# BSPD.net
KiCad netlist of a schematic drawn in Altium Designer
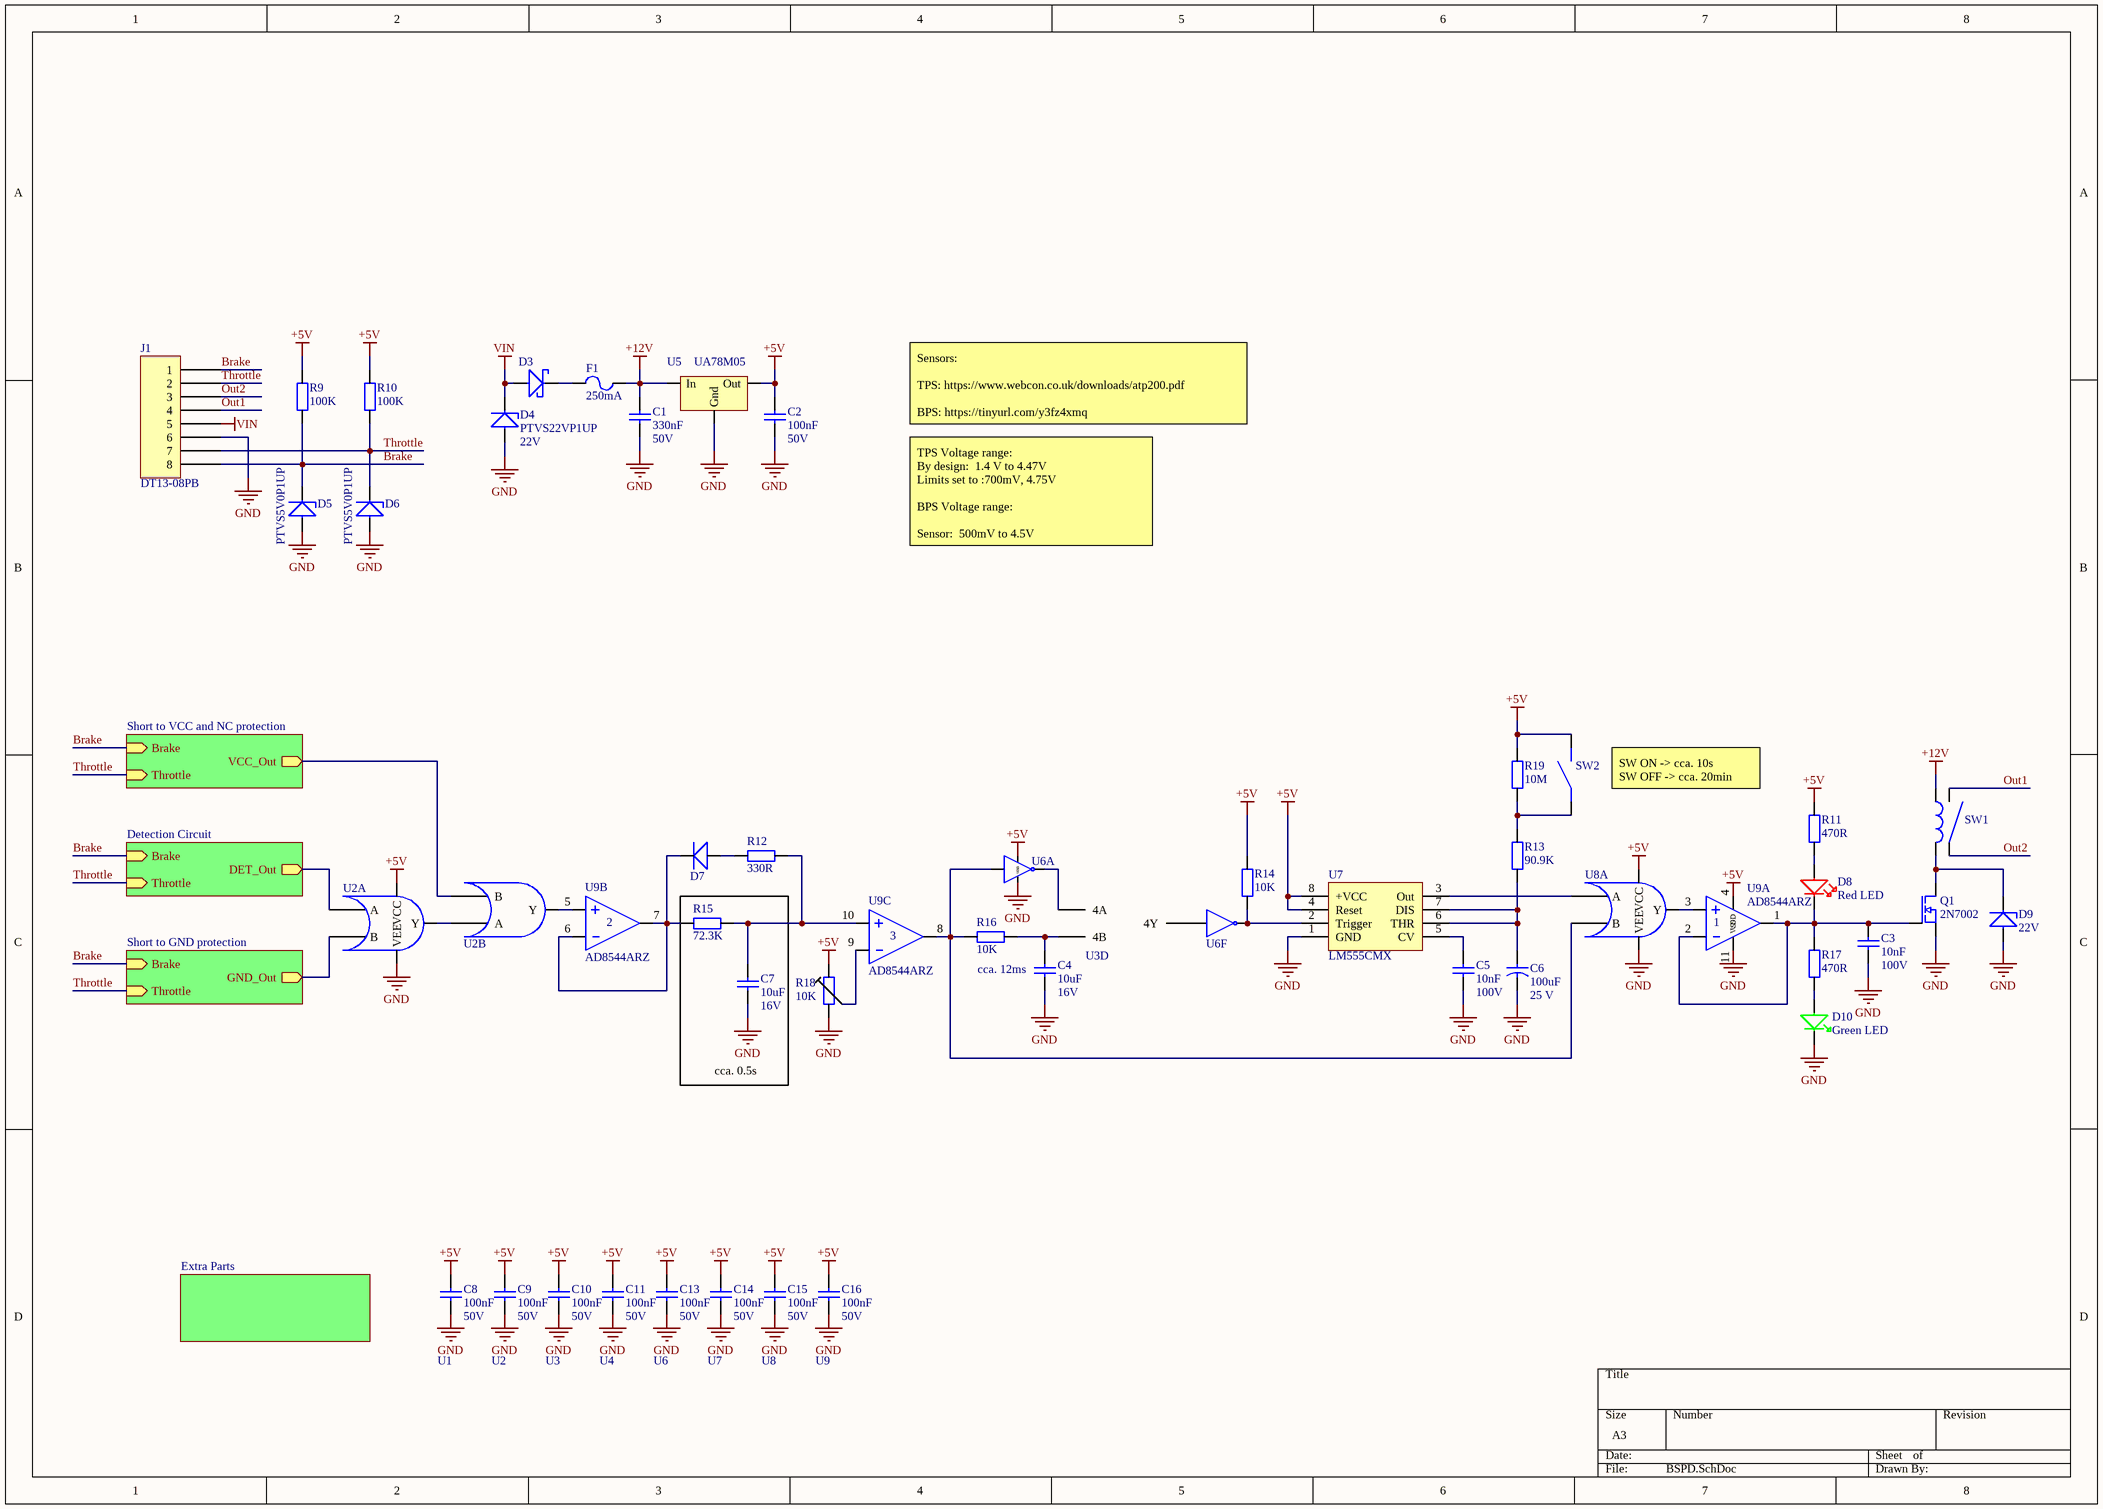
[diagram p0: BSPD.SchDoc]

(export (version "E")
  (design (tool "Eeschema 10.0.6"))
  (components
    (comp (ref "C1")
      (value "330nF")
      (footprint "CAPC320X160X90L50N")
      (fields
        (field (name "PART NUMBER") "C_1206_330nF_50V")
        (field (name "VOLTAGE RATING") "50V")
        (field (name "MANUFACTURER PART NUMBER") "1206B334K500CT")
      )
      (libsource (lib "FR") (part "Capacitor_NP"))
    )
    (comp (ref "C2")
      (value "100nF")
      (footprint "CAPC160X80X87L35N")
      (fields
        (field (name "PART NUMBER") "C_0603_100nF_50V")
        (field (name "VOLTAGE RATING") "50V")
        (field (name "MANUFACTURER PART NUMBER") "CC0603MRY5V9BB104")
      )
      (libsource (lib "FR") (part "Capacitor_NP"))
    )
    (comp (ref "C3")
      (value "10nF")
      (footprint "CAPC160X80X87L35N")
      (fields
        (field (name "PART NUMBER") "C_0603_10nF_100V")
        (field (name "VOLTAGE RATING") "100V")
        (field (name "MANUFACTURER PART NUMBER") "885012206114")
      )
      (libsource (lib "FR") (part "Capacitor_NP"))
    )
    (comp (ref "C4")
      (value "10uF")
      (footprint "CAPC160X80X90L40N")
      (fields
        (field (name "PART NUMBER") "C_0603_10uF_16V")
        (field (name "VOLTAGE RATING") "16V")
        (field (name "MANUFACTURER PART NUMBER") "GRM188R61C106KAALD")
      )
      (libsource (lib "FR") (part "Capacitor_NP"))
    )
    (comp (ref "C5")
      (value "10nF")
      (footprint "CAPC160X80X87L35N")
      (fields
        (field (name "PART NUMBER") "C_0603_10nF_100V")
        (field (name "VOLTAGE RATING") "100V")
        (field (name "MANUFACTURER PART NUMBER") "885012206114")
      )
      (libsource (lib "FR") (part "Capacitor_NP"))
    )
    (comp (ref "C6")
      (value "100uF")
      (footprint "CAPAE660X770D660L220X65N")
      (fields
        (field (name "PART NUMBER") "C_100uF_25V")
        (field (name "VOLTAGE RATING") "25 V")
        (field (name "MANUFACTURER PART NUMBER") "865080445010")
      )
      (libsource (lib "FR") (part "Capacitor_P"))
    )
    (comp (ref "C7")
      (value "10uF")
      (footprint "CAPC160X80X90L40N")
      (fields
        (field (name "PART NUMBER") "C_0603_10uF_16V")
        (field (name "VOLTAGE RATING") "16V")
        (field (name "MANUFACTURER PART NUMBER") "GRM188R61C106KAALD")
      )
      (libsource (lib "FR") (part "Capacitor_NP"))
    )
    (comp (ref "C8")
      (value "100nF")
      (footprint "CAPC160X80X87L35N")
      (fields
        (field (name "PART NUMBER") "C_0603_100nF_50V")
        (field (name "VOLTAGE RATING") "50V")
        (field (name "MANUFACTURER PART NUMBER") "CC0603MRY5V9BB104")
      )
      (libsource (lib "FR") (part "Capacitor_NP"))
    )
    (comp (ref "C9")
      (value "100nF")
      (footprint "CAPC160X80X87L35N")
      (fields
        (field (name "PART NUMBER") "C_0603_100nF_50V")
        (field (name "VOLTAGE RATING") "50V")
        (field (name "MANUFACTURER PART NUMBER") "CC0603MRY5V9BB104")
      )
      (libsource (lib "FR") (part "Capacitor_NP"))
    )
    (comp (ref "C10")
      (value "100nF")
      (footprint "CAPC160X80X87L35N")
      (fields
        (field (name "PART NUMBER") "C_0603_100nF_50V")
        (field (name "VOLTAGE RATING") "50V")
        (field (name "MANUFACTURER PART NUMBER") "CC0603MRY5V9BB104")
      )
      (libsource (lib "FR") (part "Capacitor_NP"))
    )
    (comp (ref "C11")
      (value "100nF")
      (footprint "CAPC160X80X87L35N")
      (fields
        (field (name "PART NUMBER") "C_0603_100nF_50V")
        (field (name "VOLTAGE RATING") "50V")
        (field (name "MANUFACTURER PART NUMBER") "CC0603MRY5V9BB104")
      )
      (libsource (lib "FR") (part "Capacitor_NP"))
    )
    (comp (ref "C13")
      (value "100nF")
      (footprint "CAPC160X80X87L35N")
      (fields
        (field (name "PART NUMBER") "C_0603_100nF_50V")
        (field (name "VOLTAGE RATING") "50V")
        (field (name "MANUFACTURER PART NUMBER") "CC0603MRY5V9BB104")
      )
      (libsource (lib "FR") (part "Capacitor_NP"))
    )
    (comp (ref "C14")
      (value "100nF")
      (footprint "CAPC160X80X87L35N")
      (fields
        (field (name "PART NUMBER") "C_0603_100nF_50V")
        (field (name "VOLTAGE RATING") "50V")
        (field (name "MANUFACTURER PART NUMBER") "CC0603MRY5V9BB104")
      )
      (libsource (lib "FR") (part "Capacitor_NP"))
    )
    (comp (ref "C15")
      (value "100nF")
      (footprint "CAPC160X80X87L35N")
      (fields
        (field (name "PART NUMBER") "C_0603_100nF_50V")
        (field (name "VOLTAGE RATING") "50V")
        (field (name "MANUFACTURER PART NUMBER") "CC0603MRY5V9BB104")
      )
      (libsource (lib "FR") (part "Capacitor_NP"))
    )
    (comp (ref "C16")
      (value "100nF")
      (footprint "CAPC160X80X87L35N")
      (fields
        (field (name "PART NUMBER") "C_0603_100nF_50V")
        (field (name "VOLTAGE RATING") "50V")
        (field (name "MANUFACTURER PART NUMBER") "CC0603MRY5V9BB104")
      )
      (libsource (lib "FR") (part "Capacitor_NP"))
    )
    (comp (ref "D3")
      (value "MBR0540")
      (footprint "SOD375X160X128L31X60N")
      (libsource (lib "FR") (part "S_Diode"))
    )
    (comp (ref "D4")
      (value "PTVS22VP1UP")
      (footprint "SODFL470X250X110L130X175N")
      (fields
        (field (name "PART NUMBER") "TVS_22V")
        (field (name "STAND-OFF VOLTAGE") "22V")
        (field (name "MANUFACTURER PART NUMBER") "PTVS22VP1UP,115")
      )
      (libsource (lib "FR") (part "TVS_Diode"))
    )
    (comp (ref "D5")
      (value "PTVS5V0P1UP")
      (footprint "SODFL470X250X110L130X175N")
      (fields
        (field (name "PART NUMBER") "TVS_5V")
        (field (name "MANUFACTURER PART NUMBER") "PTVS5V0P1UP,115")
      )
      (libsource (lib "FR") (part "TVS_Diode"))
    )
    (comp (ref "D6")
      (value "PTVS5V0P1UP")
      (footprint "SODFL470X250X110L130X175N")
      (fields
        (field (name "PART NUMBER") "TVS_5V")
        (field (name "MANUFACTURER PART NUMBER") "PTVS5V0P1UP,115")
      )
      (libsource (lib "FR") (part "TVS_Diode"))
    )
    (comp (ref "D7")
      (value "MMDL6050T1G")
      (footprint "SOD250X125X100L13X32N")
      (libsource (lib "FR") (part "Diode"))
    )
    (comp (ref "D8")
      (value "Red LED")
      (footprint "LEDC160X80X50L30N")
      (fields
        (field (name "PART NUMBER") "LED_Red_60mcd")
        (field (name "MANUFACTURER PART NUMBER") "150060SS75000")
      )
      (libsource (lib "FR") (part "LED_Red"))
    )
    (comp (ref "D9")
      (value "PTVS22VP1UP")
      (footprint "SODFL470X250X110L130X175N")
      (fields
        (field (name "PART NUMBER") "TVS_22V")
        (field (name "STAND-OFF VOLTAGE") "22V")
        (field (name "MANUFACTURER PART NUMBER") "PTVS22VP1UP,115")
      )
      (libsource (lib "FR") (part "TVS_Diode"))
    )
    (comp (ref "D10")
      (value "Green LED")
      (footprint "LEDC160X80X50L30N")
      (fields
        (field (name "PART NUMBER") "LED_Green_20mcd@12V,1.4K")
        (field (name "MANUFACTURER PART NUMBER") "150060VS55040")
      )
      (libsource (lib "FR") (part "LED_Green"))
    )
    (comp (ref "F1")
      (value "250mA")
      (footprint "FUSC325X165X75L42N")
      (fields
        (field (name "PART NUMBER") "F_250mA")
        (field (name "TRIPPING CURRENT") "250mA")
        (field (name "MANUFACTURER PART NUMBER") "0ZCJ0025FF2E")
      )
      (libsource (lib "FR") (part "Fuse"))
    )
    (comp (ref "J1")
      (value "DT13-08PB")
      (footprint "DT13-08PB")
      (fields (field (name "PART NUMBER") "DT13-08PB 2x4"))
      (libsource (lib "FR") (part "Connector_1x8"))
    )
    (comp (ref "Q1")
      (value "2N7002")
      (footprint "SOT23-3P95_230X110L30X43N")
      (fields (field (name "PART NUMBER") "Q_N_GSD"))
      (libsource (lib "FR") (part "Q_N_GSD"))
    )
    (comp (ref "R9")
      (value "100K")
      (footprint "RESC160X80X50L30N")
      (fields
        (field (name "PART NUMBER") "R_0603_100K_0W1_C")
        (field (name "MANUFACTURER PART NUMBER") "CRCW0603100KFKEAC")
      )
      (libsource (lib "FR") (part "Resistor"))
    )
    (comp (ref "R10")
      (value "100K")
      (footprint "RESC160X80X50L30N")
      (fields
        (field (name "PART NUMBER") "R_0603_100K_0W1_C")
        (field (name "MANUFACTURER PART NUMBER") "CRCW0603100KFKEAC")
      )
      (libsource (lib "FR") (part "Resistor"))
    )
    (comp (ref "R11")
      (value "470R")
      (footprint "RESC160X80X50L30N")
      (fields
        (field (name "PART NUMBER") "R_0603_470R_0W33")
        (field (name "MANUFACTURER PART NUMBER") "CRCW0603470RJNEAC")
      )
      (libsource (lib "FR") (part "Resistor"))
    )
    (comp (ref "R12")
      (value "330R")
      (footprint "RESC160X80X50L30N")
      (fields
        (field (name "PART NUMBER") "R_0603_330R_0W1")
        (field (name "MANUFACTURER PART NUMBER") "CRCW0603330RFKEAC")
      )
      (libsource (lib "FR") (part "Resistor"))
    )
    (comp (ref "R13")
      (value "90.9K")
      (footprint "RESC160X80X55L25N")
      (fields
        (field (name "PART NUMBER") "R_0603_90.9K_0W1")
        (field (name "MANUFACTURER PART NUMBER") "RC0603FR-0790K9L")
      )
      (libsource (lib "FR") (part "Resistor"))
    )
    (comp (ref "R14")
      (value "10K")
      (footprint "RESC160X80X50L30N")
      (fields
        (field (name "PART NUMBER") "R_0603_10K_0W062_P")
        (field (name "MANUFACTURER PART NUMBER") "APC0603B10K0N")
      )
      (libsource (lib "FR") (part "Resistor"))
    )
    (comp (ref "R15")
      (value "72.3K")
      (footprint "RESC160X80X60L30N")
      (fields
        (field (name "PART NUMBER") "R_0603_72.3K_0W062")
        (field (name "MANUFACTURER PART NUMBER") "RN731JTTD7232D100")
      )
      (libsource (lib "FR") (part "Resistor"))
    )
    (comp (ref "R16")
      (value "10K")
      (footprint "RESC160X80X50L30N")
      (fields
        (field (name "PART NUMBER") "R_0603_10K_0W062_P")
        (field (name "MANUFACTURER PART NUMBER") "APC0603B10K0N")
      )
      (libsource (lib "FR") (part "Resistor"))
    )
    (comp (ref "R17")
      (value "470R")
      (footprint "RESC160X80X50L30N")
      (fields
        (field (name "PART NUMBER") "R_0603_470R_0W33")
        (field (name "MANUFACTURER PART NUMBER") "CRCW0603470RJNEAC")
      )
      (libsource (lib "FR") (part "Resistor"))
    )
    (comp (ref "R18")
      (value "10K")
      (footprint "RESDFN3_475X200X100L160X130N")
      (fields
        (field (name "PART NUMBER") "Trimmer_10K_0W250")
        (field (name "MANUFACTURER PART NUMBER") "PVG5A103C03B00")
      )
      (libsource (lib "FR") (part "Trimmer"))
    )
    (comp (ref "R19")
      (value "10M")
      (footprint "RESC160X80X55L30N")
      (fields
        (field (name "PART NUMBER") "R_0603_10M_0W1")
        (field (name "MANUFACTURER PART NUMBER") "CRCW060310M0JNEAC")
      )
      (libsource (lib "FR") (part "Resistor"))
    )
    (comp (ref "SW1")
      (value "SPST-NO")
      (footprint "655414191282")
      (fields
        (field (name "PART NUMBER") "Relay_Non-L_TH")
        (field (name "MANUFACTURER PART NUMBER") "4-1419128-2")
      )
      (libsource (lib "FR") (part "Relay_NO"))
    )
    (comp (ref "SW2")
      (value "DS04-254-2-01BK-SMT-TR")
      (footprint "SW_DS04-254-2-01BK-SMT-TR")
      (fields (field (name "PART NUMBER") "Switch_1P"))
      (libsource (lib "FR") (part "SW"))
    )
    (comp (ref "U2")
      (value "CD4071BM")
      (footprint "SOIC14P127_865X600X175L70X42N")
      (libsource (lib "FR") (part "HEF4071B"))
    )
    (comp (ref "U3")
      (value "HEF4081BT")
      (footprint "SOIC14P127_865X600X175L70X42N")
      (fields (field (name "MANUFACTURER PART NUMBER") "HEF4081BT,653"))
      (libsource (lib "FR") (part "HEF4081BT"))
    )
    (comp (ref "U5")
      (value "UA78M05")
      (footprint "SOT223-4P230_700X180L80X75N")
      (fields (field (name "MANUFACTURER PART NUMBER") "UA78M05CDCYR"))
      (libsource (lib "FR") (part "V_REG"))
    )
    (comp (ref "U6")
      (value "HCF40106YM013TR")
      (footprint "SOIC14P127_865X600X175L88X40N")
      (fields (field (name "PART NUMBER") "HCF40106"))
      (libsource (lib "FR") (part "HCF40106"))
    )
    (comp (ref "U7")
      (value "LM555CMX")
      (footprint "SOIC8P127_490X599X175L104X41N")
      (fields (field (name "PART NUMBER") "LM555") (field (name "MANUFACTURER PART NUMBER") "LM555CMX/NOPB"))
      (libsource (lib "FR") (part "LM555"))
    )
    (comp (ref "U8")
      (value "CD4071BM")
      (footprint "SOIC14P127_865X600X175L70X42N")
      (libsource (lib "FR") (part "HEF4071B"))
    )
    (comp (ref "U9")
      (value "AD8544ARZ")
      (footprint "SOIC14P127_865X600X175L83X41N")
      (fields
        (field (name "PART NUMBER") "AD8544")
        (field (name "MANUFACTURER PART NUMBER") "AD8544ARZ-REEL")
      )
      (libsource (lib "FR") (part "AD8544"))
    )
  )
  (nets
    (net (code "1") (name "+5V") (class "Default")
      (node (ref "C10") (pin "1") (pinfunction "1_1") (pintype "passive"))
      (node (ref "C11") (pin "1") (pinfunction "1_1") (pintype "passive"))
      (node (ref "C13") (pin "1") (pinfunction "1_1") (pintype "passive"))
      (node (ref "C14") (pin "1") (pinfunction "1_1") (pintype "passive"))
      (node (ref "C15") (pin "1") (pinfunction "1_1") (pintype "passive"))
      (node (ref "C16") (pin "1") (pinfunction "1_1") (pintype "passive"))
      (node (ref "C2") (pin "2") (pinfunction "2_2") (pintype "passive"))
      (node (ref "C8") (pin "1") (pinfunction "1_1") (pintype "passive"))
      (node (ref "C9") (pin "1") (pinfunction "1_1") (pintype "passive"))
      (node (ref "R10") (pin "2") (pinfunction "2_2") (pintype "passive"))
      (node (ref "R11") (pin "1") (pinfunction "1_1") (pintype "passive"))
      (node (ref "R14") (pin "2") (pinfunction "2_2") (pintype "passive"))
      (node (ref "R18") (pin "3") (pinfunction "3_3") (pintype "passive"))
      (node (ref "R19") (pin "1") (pinfunction "1_1") (pintype "passive"))
      (node (ref "R9") (pin "2") (pinfunction "2_2") (pintype "passive"))
      (node (ref "SW2") (pin "2") (pinfunction "2_2") (pintype "passive"))
      (node (ref "U2") (pin "14") (pinfunction "VCC_14") (pintype "passive"))
      (node (ref "U5") (pin "3") (pinfunction "Out_3") (pintype "passive"))
      (node (ref "U6") (pin "14") (pinfunction "VDD_14") (pintype "passive"))
      (node (ref "U7") (pin "4") (pinfunction "Reset_4") (pintype "passive"))
      (node (ref "U7") (pin "8") (pinfunction "+VCC_8") (pintype "passive"))
      (node (ref "U8") (pin "14") (pinfunction "VCC_14") (pintype "passive"))
      (node (ref "U9") (pin "4") (pinfunction "VDD_4") (pintype "power_in"))
    )
    (net (code "2") (name "+12V") (class "Default")
      (node (ref "C1") (pin "2") (pinfunction "2_2") (pintype "passive"))
      (node (ref "F1") (pin "2") (pinfunction "2_2") (pintype "passive"))
      (node (ref "SW1") (pin "1") (pinfunction "1_1") (pintype "passive"))
      (node (ref "U5") (pin "1") (pinfunction "In_1") (pintype "passive"))
    )
    (net (code "3") (name "/Brake") (class "Default")
      (node (ref "D5") (pin "C") (pinfunction "2_C") (pintype "passive"))
      (node (ref "J1") (pin "1") (pinfunction "1_1") (pintype "passive"))
      (node (ref "J1") (pin "8") (pinfunction "8_8") (pintype "passive"))
      (node (ref "R9") (pin "1") (pinfunction "1_1") (pintype "passive"))
    )
    (net (code "4") (name "/DET_Out") (class "Default")
      (node (ref "U2") (pin "1") (pinfunction "A_1") (pintype "passive"))
    )
    (net (code "5") (name "/GND_Out") (class "Default")
      (node (ref "U2") (pin "2") (pinfunction "B_2") (pintype "passive"))
    )
    (net (code "6") (name "/Out1") (class "Default")
      (node (ref "J1") (pin "4") (pinfunction "4_4") (pintype "passive"))
      (node (ref "SW1") (pin "3") (pinfunction "3_3") (pintype "passive"))
    )
    (net (code "7") (name "/Out2") (class "Default")
      (node (ref "J1") (pin "3") (pinfunction "3_3") (pintype "passive"))
      (node (ref "SW1") (pin "4") (pinfunction "4_4") (pintype "passive"))
    )
    (net (code "8") (name "/Throttle") (class "Default")
      (node (ref "D6") (pin "C") (pinfunction "2_C") (pintype "passive"))
      (node (ref "J1") (pin "2") (pinfunction "2_2") (pintype "passive"))
      (node (ref "J1") (pin "7") (pinfunction "7_7") (pintype "passive"))
      (node (ref "R10") (pin "1") (pinfunction "1_1") (pintype "passive"))
    )
    (net (code "9") (name "/VCC_Out") (class "Default")
      (node (ref "U2") (pin "6") (pinfunction "B_6") (pintype "passive"))
    )
    (net (code "10") (name "GND") (class "Default")
      (node (ref "C1") (pin "1") (pinfunction "1_1") (pintype "passive"))
      (node (ref "C10") (pin "2") (pinfunction "2_2") (pintype "passive"))
      (node (ref "C11") (pin "2") (pinfunction "2_2") (pintype "passive"))
      (node (ref "C13") (pin "2") (pinfunction "2_2") (pintype "passive"))
      (node (ref "C14") (pin "2") (pinfunction "2_2") (pintype "passive"))
      (node (ref "C15") (pin "2") (pinfunction "2_2") (pintype "passive"))
      (node (ref "C16") (pin "2") (pinfunction "2_2") (pintype "passive"))
      (node (ref "C2") (pin "1") (pinfunction "1_1") (pintype "passive"))
      (node (ref "C3") (pin "1") (pinfunction "1_1") (pintype "passive"))
      (node (ref "C4") (pin "2") (pinfunction "2_2") (pintype "passive"))
      (node (ref "C5") (pin "1") (pinfunction "1_1") (pintype "passive"))
      (node (ref "C6") (pin "2") (pinfunction "2_2") (pintype "passive"))
      (node (ref "C7") (pin "2") (pinfunction "2_2") (pintype "passive"))
      (node (ref "C8") (pin "2") (pinfunction "2_2") (pintype "passive"))
      (node (ref "C9") (pin "2") (pinfunction "2_2") (pintype "passive"))
      (node (ref "D10") (pin "C") (pinfunction "C_C") (pintype "passive"))
      (node (ref "D4") (pin "A") (pinfunction "A_A") (pintype "passive"))
      (node (ref "D5") (pin "A") (pinfunction "A_A") (pintype "passive"))
      (node (ref "D6") (pin "A") (pinfunction "A_A") (pintype "passive"))
      (node (ref "D9") (pin "A") (pinfunction "A_A") (pintype "passive"))
      (node (ref "J1") (pin "6") (pinfunction "6_6") (pintype "passive"))
      (node (ref "Q1") (pin "2") (pinfunction "S_2") (pintype "passive"))
      (node (ref "R18") (pin "1") (pinfunction "1_1") (pintype "passive"))
      (node (ref "U2") (pin "7") (pinfunction "VEE_7") (pintype "passive"))
      (node (ref "U5") (pin "2") (pinfunction "Gnd_2") (pintype "passive"))
      (node (ref "U6") (pin "7") (pinfunction "VSS_7") (pintype "passive"))
      (node (ref "U7") (pin "1") (pinfunction "GND_1") (pintype "passive"))
      (node (ref "U8") (pin "7") (pinfunction "VEE_7") (pintype "passive"))
      (node (ref "U9") (pin "11") (pinfunction "VSS_11") (pintype "power_in"))
    )
    (net (code "11") (name "Net-(C7-Pad1)") (class "Default")
      (node (ref "C7") (pin "1") (pinfunction "1_1") (pintype "passive"))
      (node (ref "R12") (pin "1") (pinfunction "1_1") (pintype "passive"))
      (node (ref "R15") (pin "1") (pinfunction "1_1") (pintype "passive"))
      (node (ref "U9") (pin "10") (pintype "passive"))
    )
    (net (code "12") (name "Net-(D3-2)") (class "Default")
      (node (ref "D3") (pin "C") (pinfunction "2_C") (pintype "passive"))
      (node (ref "F1") (pin "1") (pinfunction "1_1") (pintype "passive"))
    )
    (net (code "13") (name "Net-(D7-2)") (class "Default")
      (node (ref "D7") (pin "C") (pinfunction "2_C") (pintype "passive"))
      (node (ref "R15") (pin "2") (pinfunction "2_2") (pintype "passive"))
      (node (ref "U9") (pin "6") (pintype "passive"))
      (node (ref "U9") (pin "7") (pintype "passive"))
    )
    (net (code "14") (name "Net-(D7-PadA)") (class "Default")
      (node (ref "D7") (pin "A") (pinfunction "A_A") (pintype "passive"))
      (node (ref "R12") (pin "2") (pinfunction "2_2") (pintype "passive"))
    )
    (net (code "15") (name "Net-(D8-PadA)") (class "Default")
      (node (ref "D8") (pin "A") (pinfunction "A_A") (pintype "passive"))
      (node (ref "R11") (pin "2") (pinfunction "2_2") (pintype "passive"))
    )
    (net (code "16") (name "Net-(D9-2)") (class "Default")
      (node (ref "D9") (pin "C") (pinfunction "2_C") (pintype "passive"))
      (node (ref "Q1") (pin "3") (pinfunction "D_3") (pintype "passive"))
      (node (ref "SW1") (pin "2") (pinfunction "2_2") (pintype "passive"))
    )
    (net (code "17") (name "Net-(D10-PadA)") (class "Default")
      (node (ref "D10") (pin "A") (pinfunction "A_A") (pintype "passive"))
      (node (ref "R17") (pin "2") (pinfunction "2_2") (pintype "passive"))
    )
    (net (code "18") (name "Net-(Q1-G)") (class "Default")
      (node (ref "C3") (pin "2") (pinfunction "2_2") (pintype "passive"))
      (node (ref "D8") (pin "C") (pinfunction "C_C") (pintype "passive"))
      (node (ref "Q1") (pin "1") (pinfunction "G_1") (pintype "passive"))
      (node (ref "R17") (pin "1") (pinfunction "1_1") (pintype "passive"))
      (node (ref "U9") (pin "1") (pintype "passive"))
      (node (ref "U9") (pin "2") (pintype "passive"))
    )
    (net (code "19") (name "Net-(R13-Pad2)") (class "Default")
      (node (ref "R13") (pin "2") (pinfunction "2_2") (pintype "passive"))
      (node (ref "R19") (pin "2") (pinfunction "2_2") (pintype "passive"))
      (node (ref "SW2") (pin "1") (pinfunction "1_1") (pintype "passive"))
    )
    (net (code "20") (name "Net-(R18-Pad2)") (class "Default")
      (node (ref "R18") (pin "2") (pinfunction "2_2") (pintype "passive"))
      (node (ref "U9") (pin "9") (pintype "passive"))
    )
    (net (code "21") (name "Net-(U2A-Y)") (class "Default")
      (node (ref "U2") (pin "3") (pinfunction "Y_3") (pintype "passive"))
      (node (ref "U2") (pin "5") (pinfunction "A_5") (pintype "passive"))
    )
    (net (code "22") (name "Net-(U2B-Y)") (class "Default")
      (node (ref "U2") (pin "4") (pinfunction "Y_4") (pintype "passive"))
      (node (ref "U9") (pin "5") (pintype "passive"))
    )
    (net (code "23") (name "Net-(U3D-4A)") (class "Default")
      (node (ref "U3") (pin "12") (pinfunction "4A_12") (pintype "passive"))
      (node (ref "U6") (pin "2") (pinfunction "G_2") (pintype "passive"))
    )
    (net (code "24") (name "Net-(U3D-4B)") (class "Default")
      (node (ref "C4") (pin "1") (pinfunction "1_1") (pintype "passive"))
      (node (ref "R16") (pin "1") (pinfunction "1_1") (pintype "passive"))
      (node (ref "U3") (pin "13") (pinfunction "4B_13") (pintype "passive"))
    )
    (net (code "25") (name "Net-(U3D-4Y)") (class "Default")
      (node (ref "U3") (pin "11") (pinfunction "4Y_11") (pintype "passive"))
      (node (ref "U6") (pin "13") (pinfunction "F_13") (pintype "passive"))
    )
    (net (code "26") (name "Net-(U6A-A)") (class "Default")
      (node (ref "R16") (pin "2") (pinfunction "2_2") (pintype "passive"))
      (node (ref "U6") (pin "1") (pinfunction "A_1") (pintype "passive"))
      (node (ref "U8") (pin "2") (pinfunction "B_2") (pintype "passive"))
      (node (ref "U9") (pin "8") (pintype "passive"))
    )
    (net (code "27") (name "Net-(U6F-L)") (class "Default")
      (node (ref "R14") (pin "1") (pinfunction "1_1") (pintype "passive"))
      (node (ref "U6") (pin "12") (pinfunction "L_12") (pintype "passive"))
      (node (ref "U7") (pin "2") (pinfunction "Trigger_2") (pintype "passive"))
    )
    (net (code "28") (name "Net-(U7-CV)") (class "Default")
      (node (ref "C5") (pin "2") (pinfunction "2_2") (pintype "passive"))
      (node (ref "U7") (pin "5") (pinfunction "CV_5") (pintype "passive"))
    )
    (net (code "29") (name "Net-(U7-DIS)") (class "Default")
      (node (ref "C6") (pin "1") (pinfunction "1_1") (pintype "passive"))
      (node (ref "R13") (pin "1") (pinfunction "1_1") (pintype "passive"))
      (node (ref "U7") (pin "6") (pinfunction "THR_6") (pintype "passive"))
      (node (ref "U7") (pin "7") (pinfunction "DIS_7") (pintype "passive"))
    )
    (net (code "30") (name "Net-(U7-Out)") (class "Default")
      (node (ref "U7") (pin "3") (pinfunction "Out_3") (pintype "passive"))
      (node (ref "U8") (pin "1") (pinfunction "A_1") (pintype "passive"))
    )
    (net (code "31") (name "Net-(U8A-Y)") (class "Default")
      (node (ref "U8") (pin "3") (pinfunction "Y_3") (pintype "passive"))
      (node (ref "U9") (pin "3") (pintype "passive"))
    )
    (net (code "32") (name "VIN") (class "Default")
      (node (ref "D3") (pin "A") (pinfunction "A_A") (pintype "passive"))
      (node (ref "D4") (pin "C") (pinfunction "2_C") (pintype "passive"))
      (node (ref "J1") (pin "5") (pinfunction "5_5") (pintype "passive"))
    )
  )
)
